# Regelaar.net
KiCad netlist of a schematic drawn in Altium Designer
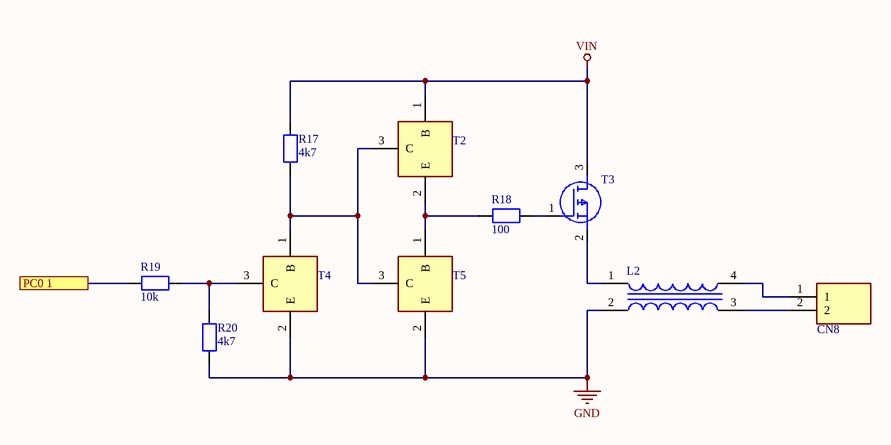
[diagram p0: Regelaar.SchDoc]

(export (version "E")
  (design (tool "Eeschema 10.0.6"))
  (components
    (comp (ref "CN8")
      (value "282836-2")
      (footprint "SamacSys:2828362")
      (description "Connector")
      (libsource (lib "Schlib1") (part "Schroefconnector 2 Pin R"))
    )
    (comp (ref "L2")
      (value "Smoorspoel commom mode")
      (footprint "SamacSys:CM2545X171B10")
      (description "Transformer CM2545X171B-10")
      (fields (field (name "MANUFACTURER_PART_NUMBER") "CM2545X171B-10"))
      (libsource (lib "Schlib1") (part "Smoorspoel commom mode"))
    )
    (comp (ref "R17")
      (value "4k7")
      (footprint "0805")
      (fields (field (name "MANUFACTURER") "Vishay Dale") (field (name "PART NUMBER") "CRCW08050000Z0EA"))
      (libsource (lib "Schlib1") (part "Resistor 0805"))
    )
    (comp (ref "R18")
      (value "100")
      (footprint "0805")
      (fields (field (name "MANUFACTURER") "Vishay Dale") (field (name "PART NUMBER") "CRCW08050000Z0EA"))
      (libsource (lib "Schlib1") (part "Resistor 0805"))
    )
    (comp (ref "R19")
      (value "10k")
      (footprint "0805")
      (fields (field (name "MANUFACTURER") "Vishay Dale") (field (name "PART NUMBER") "CRCW08050000Z0EA"))
      (libsource (lib "Schlib1") (part "Resistor 0805"))
    )
    (comp (ref "R20")
      (value "4k7")
      (footprint "0805")
      (fields (field (name "MANUFACTURER") "Vishay Dale") (field (name "PART NUMBER") "CRCW08050000Z0EA"))
      (libsource (lib "Schlib1") (part "Resistor 0805"))
    )
    (comp (ref "T2")
      (value "CMPT5551")
      (footprint "SamacSys:SOT95P230X109-3N")
      (description "Transistor")
      (fields (field (name "MANUFACTURER_PART_NUMBER") "CMPT5551 TR PBFREE"))
      (libsource (lib "Schlib1") (part "Transistor_L"))
    )
    (comp (ref "T3")
      (value "IRF9Z34NPBF")
      (footprint "SamacSys:TO254P469X1042X1967-3P")
      (description "MOSFET (P-Channel)")
      (fields (field (name "MOUSER2 PART NUMBER") "942-IRF9Z34NPBF"))
      (libsource (lib "*") (part "IRF9Z34NPBF"))
    )
    (comp (ref "T4")
      (value "CMPT5551")
      (footprint "SamacSys:SOT95P230X109-3N")
      (description "Transistor")
      (fields (field (name "MANUFACTURER_PART_NUMBER") "CMPT5551 TR PBFREE"))
      (libsource (lib "Schlib1") (part "Transistor_L"))
    )
    (comp (ref "T5")
      (value "CMPT5551")
      (footprint "SamacSys:SOT95P230X109-3N")
      (description "Transistor")
      (fields (field (name "MANUFACTURER_PART_NUMBER") "CMPT5551 TR PBFREE"))
      (libsource (lib "Schlib1") (part "Transistor_L"))
    )
  )
  (nets
    (net (code "1") (name "/PC0 1") (class "Default")
      (node (ref "R19") (pin "1") (pinfunction "1_1") (pintype "passive"))
    )
    (net (code "2") (name "GND") (class "Default")
      (node (ref "L2") (pin "2") (pinfunction "SEC+_2") (pintype "passive"))
      (node (ref "R20") (pin "1") (pinfunction "1_1") (pintype "passive"))
      (node (ref "T4") (pin "2") (pinfunction "E_2") (pintype "passive"))
      (node (ref "T5") (pin "2") (pinfunction "E_2") (pintype "passive"))
    )
    (net (code "3") (name "Net-(L2-PRI+)") (class "Default")
      (node (ref "L2") (pin "1") (pinfunction "PRI+_1") (pintype "passive"))
      (node (ref "T3") (pin "2") (pinfunction "S_2") (pintype "passive"))
    )
    (net (code "4") (name "Net-(L2-PRI-)") (class "Default")
      (node (ref "CN8") (pin "1") (pinfunction "1_1") (pintype "passive"))
      (node (ref "L2") (pin "4") (pinfunction "PRI-_4") (pintype "passive"))
    )
    (net (code "5") (name "Net-(L2-SEC-)") (class "Default")
      (node (ref "CN8") (pin "2") (pinfunction "2_2") (pintype "passive"))
      (node (ref "L2") (pin "3") (pinfunction "SEC-_3") (pintype "passive"))
    )
    (net (code "6") (name "Net-(T2-C)") (class "Default")
      (node (ref "R17") (pin "1") (pinfunction "1_1") (pintype "passive"))
      (node (ref "T2") (pin "3") (pinfunction "C_3") (pintype "passive"))
      (node (ref "T4") (pin "1") (pinfunction "B_1") (pintype "passive"))
      (node (ref "T5") (pin "3") (pinfunction "C_3") (pintype "passive"))
    )
    (net (code "7") (name "Net-(T2-E)") (class "Default")
      (node (ref "R18") (pin "1") (pinfunction "1_1") (pintype "passive"))
      (node (ref "T2") (pin "2") (pinfunction "E_2") (pintype "passive"))
      (node (ref "T5") (pin "1") (pinfunction "B_1") (pintype "passive"))
    )
    (net (code "8") (name "Net-(T3-G)") (class "Default")
      (node (ref "R18") (pin "2") (pinfunction "2_2") (pintype "passive"))
      (node (ref "T3") (pin "1") (pinfunction "G_1") (pintype "passive"))
    )
    (net (code "9") (name "Net-(T4-C)") (class "Default")
      (node (ref "R19") (pin "2") (pinfunction "2_2") (pintype "passive"))
      (node (ref "R20") (pin "2") (pinfunction "2_2") (pintype "passive"))
      (node (ref "T4") (pin "3") (pinfunction "C_3") (pintype "passive"))
    )
    (net (code "10") (name "VIN") (class "Default")
      (node (ref "R17") (pin "2") (pinfunction "2_2") (pintype "passive"))
      (node (ref "T2") (pin "1") (pinfunction "B_1") (pintype "passive"))
      (node (ref "T3") (pin "3") (pinfunction "D_3") (pintype "passive"))
    )
  )
)
